# sara-n210_breakout.net
KiCad netlist of a schematic drawn in Altium Designer
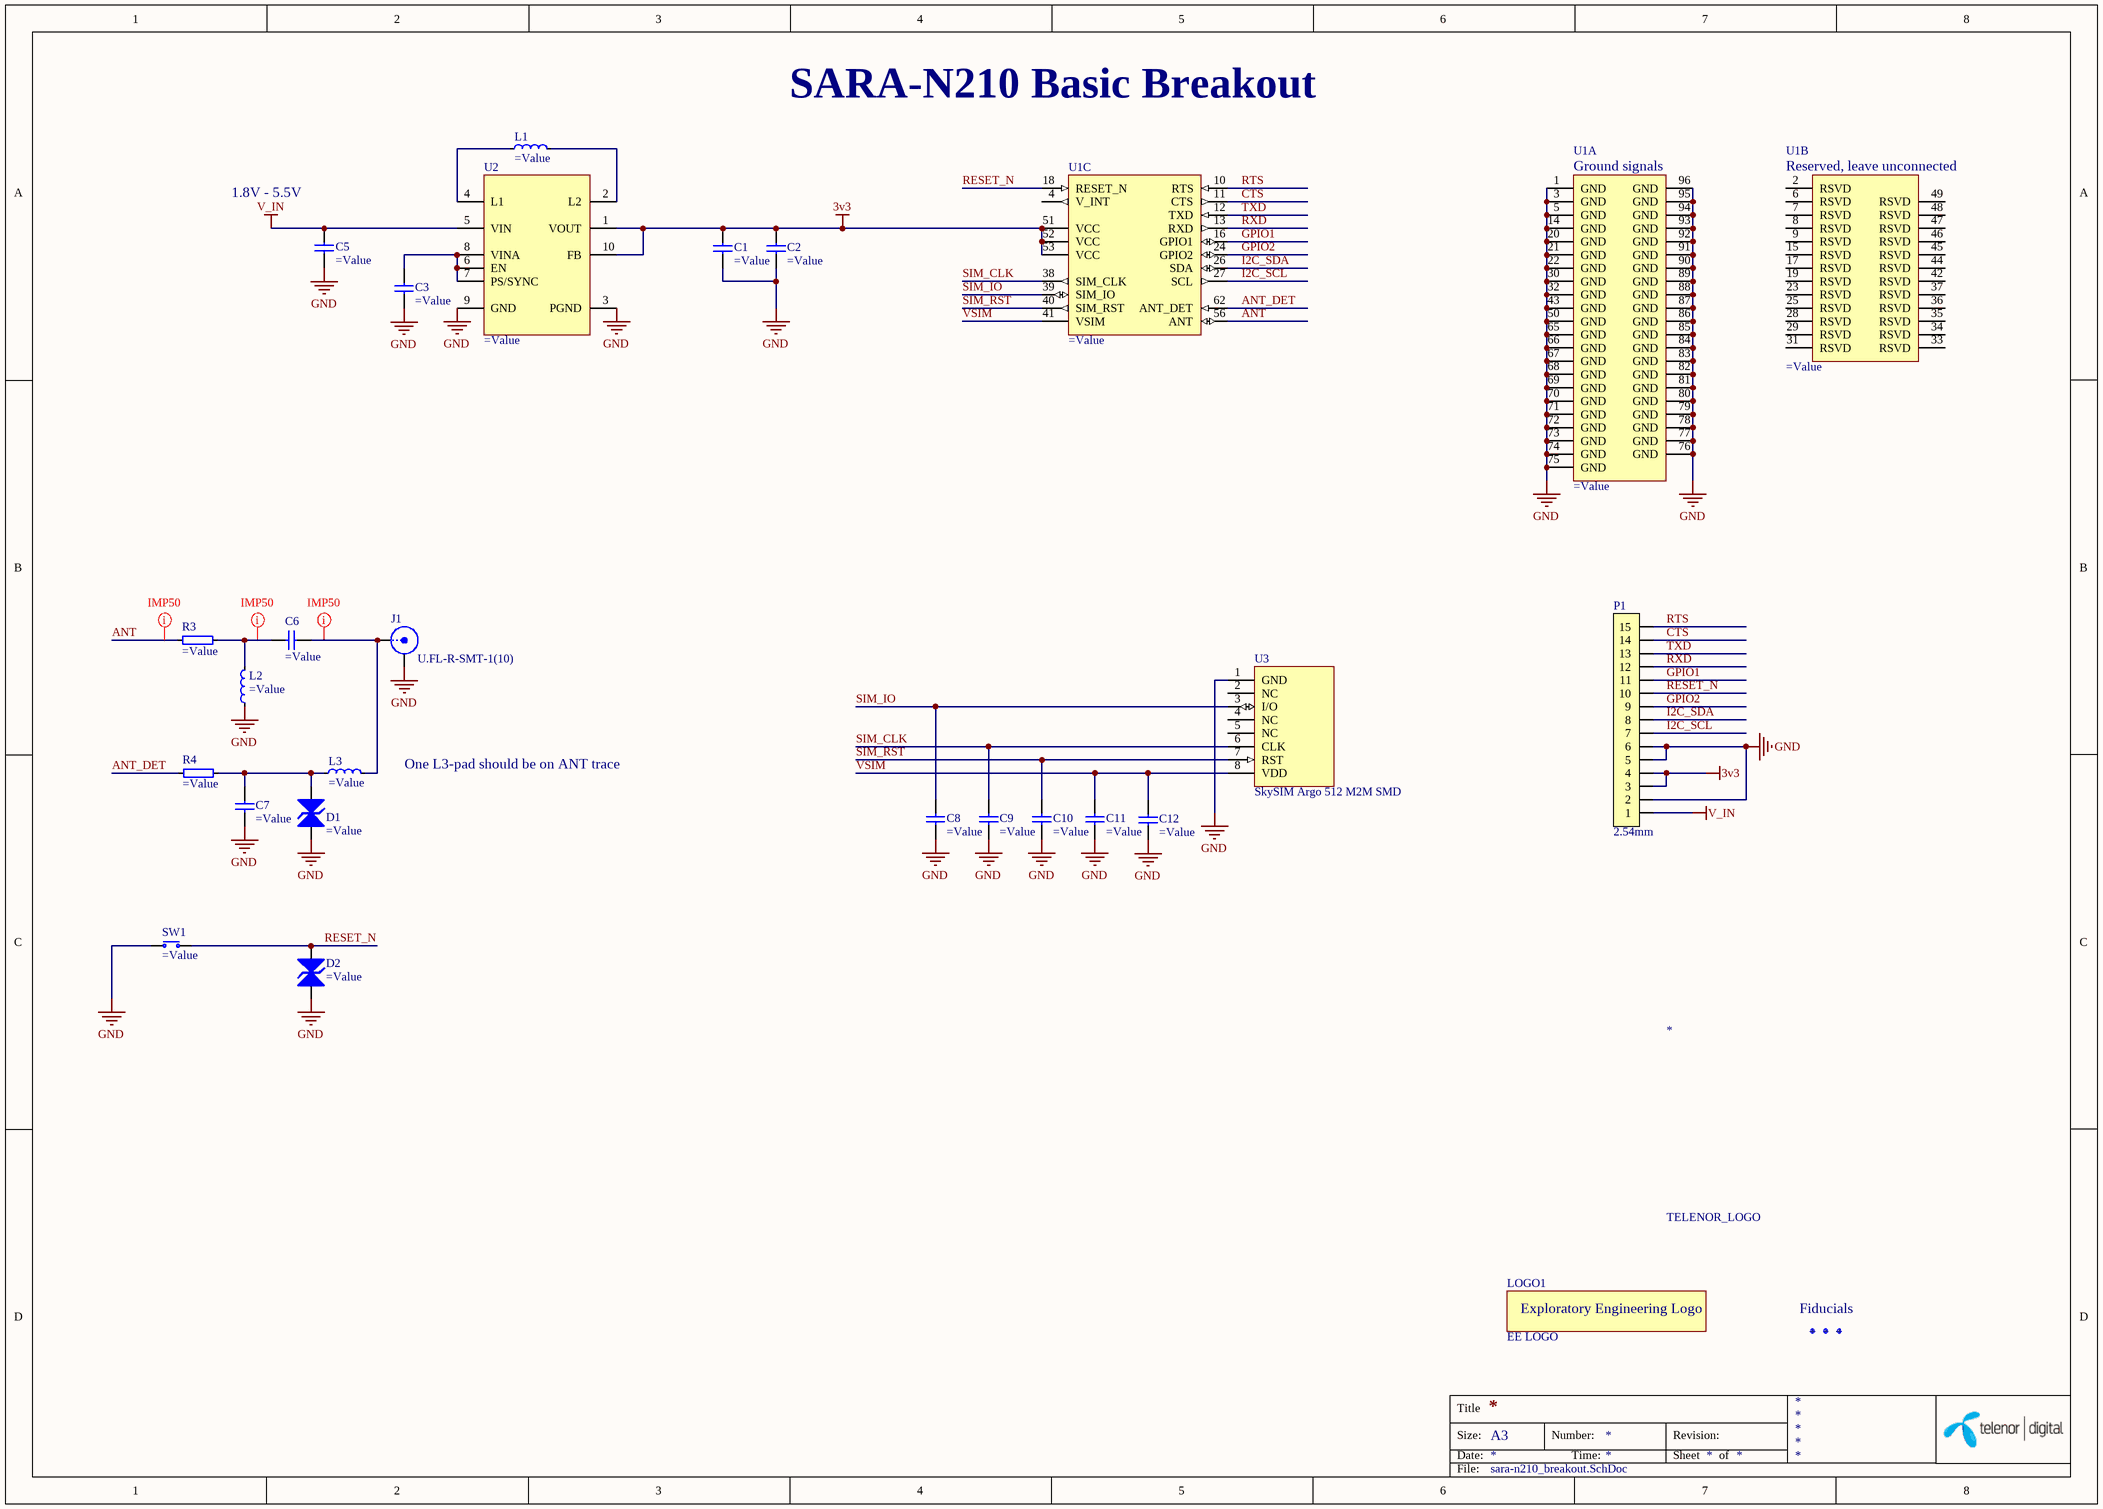
[diagram p0: sara-n210_breakout.SchDoc]

(export (version "E")
  (design (tool "Eeschema 10.0.6"))
  (components
    (comp (ref "*")
      (value "TELENOR_LOGO")
      (footprint "TELENOR_4mmx3.8mm")
      (libsource (lib "Skunkworks Library") (part "TELENOR_LOGO"))
    )
    (comp (ref "C1")
      (value "~")
      (footprint "CAPC1005X04L")
      (description "CAP CER 10UF 6.3V X5R 0402")
      (fields
        (field (name "MANUFACTURER") "Murata Electronics North America")
        (field (name "MANUFACTURER PART NUMBER") "GRM155R60J106ME15D")
      )
      (libsource (lib "Skunkworks Library") (part "GRM155R60J106ME15D"))
    )
    (comp (ref "C2")
      (value "~")
      (footprint "CAPC1005X04L")
      (description "CAP CER 10UF 6.3V X5R 0402")
      (fields
        (field (name "MANUFACTURER") "Murata Electronics North America")
        (field (name "MANUFACTURER PART NUMBER") "GRM155R60J106ME15D")
      )
      (libsource (lib "Skunkworks Library") (part "GRM155R60J106ME15D"))
    )
    (comp (ref "C3")
      (value "~")
      (footprint "CAPC1005X04L")
      (description "CAP CER 100nF 16V X7R 0402")
      (fields
        (field (name "MANUFACTURER") "Murata Electronics North America")
        (field (name "MANUFACTURER PART NUMBER") "GRM155R71C104KA88D")
      )
      (libsource (lib "Skunkworks Library") (part "GRM155R71C104KA88D"))
    )
    (comp (ref "C5")
      (value "~")
      (footprint "CAPC1005X04L")
      (description "CAP CER 10UF 6.3V X5R 0402")
      (fields
        (field (name "MANUFACTURER") "Murata Electronics North America")
        (field (name "MANUFACTURER PART NUMBER") "GRM155R60J106ME15D")
      )
      (libsource (lib "Skunkworks Library") (part "GRM155R60J106ME15D"))
    )
    (comp (ref "C6")
      (value "~")
      (footprint "CAPC1005X04L")
      (description "CAP CER 33PF 50V NP0 0402")
      (fields
        (field (name "MANUFACTURER") "Murata Electronics North America")
        (field (name "MANUFACTURER PART NUMBER") "GRM1555C1H330JZ01D")
      )
      (libsource (lib "Skunkworks Library") (part "GRM1555C1H330JZ01D"))
    )
    (comp (ref "C7")
      (value "~")
      (footprint "CAPC1005X04L")
      (description "CAP CER 27PF 50V C0G/NP0 0402")
      (fields
        (field (name "MANUFACTURER") "Murata Electronics North America")
        (field (name "MANUFACTURER PART NUMBER") "GRM1555C1H270JA01D")
      )
      (libsource (lib "Skunkworks Library") (part "GRM1555C1H270JA01D"))
    )
    (comp (ref "C8")
      (value "~")
      (footprint "CAPC1005X04L")
      (description "CAP CER 47PF 50V C0G/NP0 0402")
      (fields
        (field (name "MANUFACTURER") "Murata Electronics North America")
        (field (name "MANUFACTURER PART NUMBER") "GRM1555C1H470JA01D")
      )
      (libsource (lib "Skunkworks Library") (part "GRM1555C1H470JA01D"))
    )
    (comp (ref "C9")
      (value "~")
      (footprint "CAPC1005X04L")
      (description "CAP CER 47PF 50V C0G/NP0 0402")
      (fields
        (field (name "MANUFACTURER") "Murata Electronics North America")
        (field (name "MANUFACTURER PART NUMBER") "GRM1555C1H470JA01D")
      )
      (libsource (lib "Skunkworks Library") (part "GRM1555C1H470JA01D"))
    )
    (comp (ref "C10")
      (value "~")
      (footprint "CAPC1005X04L")
      (description "CAP CER 47PF 50V C0G/NP0 0402")
      (fields
        (field (name "MANUFACTURER") "Murata Electronics North America")
        (field (name "MANUFACTURER PART NUMBER") "GRM1555C1H470JA01D")
      )
      (libsource (lib "Skunkworks Library") (part "GRM1555C1H470JA01D"))
    )
    (comp (ref "C11")
      (value "~")
      (footprint "CAPC1005X04L")
      (description "CAP CER 47PF 50V C0G/NP0 0402")
      (fields
        (field (name "MANUFACTURER") "Murata Electronics North America")
        (field (name "MANUFACTURER PART NUMBER") "GRM1555C1H470JA01D")
      )
      (libsource (lib "Skunkworks Library") (part "GRM1555C1H470JA01D"))
    )
    (comp (ref "C12")
      (value "~")
      (footprint "CAPC1005X04L")
      (description "CAP CER 100nF 16V X7R 0402")
      (fields
        (field (name "MANUFACTURER") "Murata Electronics North America")
        (field (name "MANUFACTURER PART NUMBER") "GRM155R71C104KA88D")
      )
      (libsource (lib "Skunkworks Library") (part "GRM155R71C104KA88D"))
    )
    (comp (ref "D1")
      (value "~")
      (footprint "RESC1005X04L")
      (description "TVS DIODE 14VWM 40VC 0402")
      (fields
        (field (name "MANUFACTURER") "Littelfuse Inc.")
        (field (name "MANUFACTURER PART NUMBER") "PESD0402-140")
      )
      (libsource (lib "Skunkworks Library") (part "PESD0402-140"))
    )
    (comp (ref "D2")
      (value "~")
      (footprint "RESC1005X04L")
      (description "VARISTOR 28V 2A 0402")
      (fields
        (field (name "MANUFACTURER") "EPCOS (TDK)")
        (field (name "MANUFACTURER PART NUMBER") "B72590T8140S160")
      )
      (libsource (lib "Skunkworks Library") (part "B72590T8140S160"))
    )
    (comp (ref "Fid1")
      (value "Fiducial mark")
      (footprint "Fiducial")
      (description "Fiducial Mark")
      (fields (field (name "PART NUMBER") "Fid-Mark") (field (name "PUBLISHER") "Nordic Semiconductor"))
      (libsource (lib "Skunkworks Library") (part "Fiducial"))
    )
    (comp (ref "Fid2")
      (value "Fiducial mark")
      (footprint "Fiducial")
      (description "Fiducial Mark")
      (fields (field (name "PART NUMBER") "Fid-Mark") (field (name "PUBLISHER") "Nordic Semiconductor"))
      (libsource (lib "Skunkworks Library") (part "Fiducial"))
    )
    (comp (ref "Fid3")
      (value "Fiducial mark")
      (footprint "Fiducial")
      (description "Fiducial Mark")
      (fields (field (name "PART NUMBER") "Fid-Mark") (field (name "PUBLISHER") "Nordic Semiconductor"))
      (libsource (lib "Skunkworks Library") (part "Fiducial"))
    )
    (comp (ref "J1")
      (value "U.FL-R-SMT-1(10)")
      (footprint "COAXIAL-UFL")
      (description "CONN UMC JACK STR 50 OHM SMD")
      (fields (field (name "MANUFACTURER") "Hirose Electric Co Ltd"))
      (libsource (lib "Skunkworks Library") (part "U.FL-R-SMT-1(10)"))
    )
    (comp (ref "L1")
      (value "~")
      (footprint "INDP3030X11L")
      (description "FIXED IND 1.5UH 2.04A 88.8 MOHM")
      (fields
        (field (name "MANUFACTURER") "Murata Electronics North America")
        (field (name "MANUFACTURER PART NUMBER") "LQH3NPZ1R5MGRL")
      )
      (libsource (lib "Skunkworks Library") (part "LQH3NPZ1R5MGRL"))
    )
    (comp (ref "L2")
      (value "~")
      (footprint "INDC1005X04L")
      (description "FIXED IND 39NH 250MA 1.06 OHM")
      (fields
        (field (name "MANUFACTURER") "Murata Electronics North America")
        (field (name "MANUFACTURER PART NUMBER") "LQG15HN39NJ02D")
      )
      (libsource (lib "Skunkworks Library") (part "LQG15HN39NJ02D"))
    )
    (comp (ref "L3")
      (value "~")
      (footprint "INDC1005X04L")
      (description "FIXED IND 82NH 150MA 1.2 OHM SMD")
      (fields
        (field (name "MANUFACTURER") "Murata Electronics North America")
        (field (name "MANUFACTURER PART NUMBER") "LQG15HS82NJ02D")
      )
      (libsource (lib "Skunkworks Library") (part "LQG15HS82NJ02D"))
    )
    (comp (ref "LOGO1")
      (value "EE LOGO")
      (footprint "EE_LOGO")
      (description "Exploratory Engineering Logo Silkscreen")
      (libsource (lib "Skunkworks Library") (part "EE-LOGO"))
    )
    (comp (ref "P1")
      (value "2.54mm")
      (footprint "HDR_1x15_2.54mm_THRU")
      (description "Header, 1x15, Pitch 2.54mm, Male")
      (libsource (lib "Skunkworks Library") (part "HDR_1x15_2.54MM_MALE"))
    )
    (comp (ref "R3")
      (value "~")
      (footprint "RESC1005X04L")
      (description "RES SMD 0.0OHM JUMPER 1/16W 0402")
      (fields
        (field (name "MANUFACTURER") "Yageo")
        (field (name "MANUFACTURER PART NUMBER") "RC0402JR-070RL")
      )
      (libsource (lib "Skunkworks Library") (part "RC0402JR-070RL"))
    )
    (comp (ref "R4")
      (value "~")
      (footprint "RESC1005X04L")
      (description "RES SMD 10K OHM 1% 1/10W 0402")
      (fields
        (field (name "MANUFACTURER") "Vishay Beyschlag")
        (field (name "MANUFACTURER PART NUMBER") "MCS04020C1002FE000")
      )
      (libsource (lib "Skunkworks Library") (part "MCS04020C1002FE000"))
    )
    (comp (ref "SW1")
      (value "~")
      (footprint "RS-014R05B1-SMA10")
      (description "SWITCH TACTILE SPST-NO 0.05A 12V")
      (fields
        (field (name "MANUFACTURER") "C&K")
        (field (name "MANUFACTURER PART NUMBER") "RS-014R05B1-SMA10 RT")
      )
      (libsource (lib "Skunkworks Library") (part "RS-014R05B1-SMA10 RT"))
    )
    (comp (ref "U1")
      (value "~")
      (footprint "UB-SARA-N2")
      (description "uBlox Sara N210")
      (fields (field (name "MANUFACTURER PART NUMBER") "SARA-N210-02B"))
      (libsource (lib "Skunkworks Library") (part "SARA-N2"))
    )
    (comp (ref "U2")
      (value "~")
      (footprint "SON50P250X80_HS-11N")
      (description "IC REG BUCK BST 3.3V 0.9A 10SON")
      (fields
        (field (name "MANUFACTURER") "Texas Instruments")
        (field (name "MANUFACTURER PART NUMBER") "TPS63031DSKR")
      )
      (libsource (lib "Skunkworks Library") (part "TPS63031DSKR"))
    )
    (comp (ref "U3")
      (value "SkySIM Argo 512 M2M SMD")
      (footprint "QFN127P500X600X90_HS-9N")
      (description "SkySIM® Argo 512 M2M SMD - LTE")
      (libsource (lib "Skunkworks Library") (part "SKYSIM-ARGO-LTE-MFF2"))
    )
  )
  (nets
    (net (code "1") (name "/ANT") (class "Default")
      (node (ref "R3") (pin "1") (pinfunction "1_1") (pintype "passive"))
      (node (ref "U1") (pin "56") (pinfunction "ANT_56") (pintype "bidirectional"))
    )
    (net (code "2") (name "/ANT_DET") (class "Default")
      (node (ref "R4") (pin "1") (pinfunction "1_1") (pintype "passive"))
      (node (ref "U1") (pin "62") (pinfunction "ANT_DET_62") (pintype "input"))
    )
    (net (code "3") (name "/CTS") (class "Default")
      (node (ref "P1") (pin "14") (pinfunction "14_14") (pintype "passive"))
      (node (ref "U1") (pin "11") (pinfunction "CTS_11") (pintype "output"))
    )
    (net (code "4") (name "/GPIO1") (class "Default")
      (node (ref "P1") (pin "11") (pinfunction "11_11") (pintype "passive"))
      (node (ref "U1") (pin "16") (pinfunction "GPIO1_16") (pintype "bidirectional"))
    )
    (net (code "5") (name "/GPIO2") (class "Default")
      (node (ref "P1") (pin "9") (pinfunction "9_9") (pintype "passive"))
      (node (ref "U1") (pin "24") (pinfunction "GPIO2_24") (pintype "bidirectional"))
    )
    (net (code "6") (name "/I2C_SCL") (class "Default")
      (node (ref "P1") (pin "7") (pinfunction "7_7") (pintype "passive"))
      (node (ref "U1") (pin "27") (pinfunction "SCL_27") (pintype "output"))
    )
    (net (code "7") (name "/I2C_SDA") (class "Default")
      (node (ref "P1") (pin "8") (pinfunction "8_8") (pintype "passive"))
      (node (ref "U1") (pin "26") (pinfunction "SDA_26") (pintype "bidirectional"))
    )
    (net (code "8") (name "/RESET_N") (class "Default")
      (node (ref "D2") (pin "1") (pinfunction "A_1") (pintype "passive"))
      (node (ref "P1") (pin "10") (pinfunction "10_10") (pintype "passive"))
      (node (ref "SW1") (pin "1") (pinfunction "N.O_1") (pintype "passive"))
      (node (ref "U1") (pin "18") (pinfunction "RESET_N_18") (pintype "input"))
    )
    (net (code "9") (name "/RTS") (class "Default")
      (node (ref "P1") (pin "15") (pinfunction "15_15") (pintype "passive"))
      (node (ref "U1") (pin "10") (pinfunction "RTS_10") (pintype "input"))
    )
    (net (code "10") (name "/RXD") (class "Default")
      (node (ref "P1") (pin "12") (pinfunction "12_12") (pintype "passive"))
      (node (ref "U1") (pin "13") (pinfunction "RXD_13") (pintype "output"))
    )
    (net (code "11") (name "/SIM_CLK") (class "Default")
      (node (ref "C9") (pin "2") (pinfunction "2_2") (pintype "passive"))
      (node (ref "U1") (pin "38") (pinfunction "SIM_CLK_38") (pintype "output"))
      (node (ref "U3") (pin "6") (pinfunction "CLK_6") (pintype "passive"))
    )
    (net (code "12") (name "/SIM_IO") (class "Default")
      (node (ref "C8") (pin "2") (pinfunction "2_2") (pintype "passive"))
      (node (ref "U1") (pin "39") (pinfunction "SIM_IO_39") (pintype "bidirectional"))
      (node (ref "U3") (pin "3") (pinfunction "I/O_3") (pintype "bidirectional"))
    )
    (net (code "13") (name "/SIM_RST") (class "Default")
      (node (ref "C10") (pin "2") (pinfunction "2_2") (pintype "passive"))
      (node (ref "U1") (pin "40") (pinfunction "SIM_RST_40") (pintype "output"))
      (node (ref "U3") (pin "7") (pinfunction "RST_7") (pintype "input"))
    )
    (net (code "14") (name "/TXD") (class "Default")
      (node (ref "P1") (pin "13") (pinfunction "13_13") (pintype "passive"))
      (node (ref "U1") (pin "12") (pinfunction "TXD_12") (pintype "input"))
    )
    (net (code "15") (name "/VSIM") (class "Default")
      (node (ref "C11") (pin "2") (pinfunction "2_2") (pintype "passive"))
      (node (ref "C12") (pin "2") (pinfunction "2_2") (pintype "passive"))
      (node (ref "U1") (pin "41") (pinfunction "VSIM_41") (pintype "passive"))
      (node (ref "U3") (pin "8") (pinfunction "VDD_8") (pintype "passive"))
    )
    (net (code "16") (name "3v3") (class "Default")
      (node (ref "C1") (pin "2") (pinfunction "2_2") (pintype "passive"))
      (node (ref "C2") (pin "2") (pinfunction "2_2") (pintype "passive"))
      (node (ref "P1") (pin "3") (pinfunction "3_3") (pintype "passive"))
      (node (ref "P1") (pin "4") (pinfunction "4_4") (pintype "passive"))
      (node (ref "U1") (pin "51") (pinfunction "VCC_51") (pintype "passive"))
      (node (ref "U1") (pin "52") (pinfunction "VCC_52") (pintype "passive"))
      (node (ref "U1") (pin "53") (pinfunction "VCC_53") (pintype "passive"))
      (node (ref "U2") (pin "1") (pinfunction "VOUT_1") (pintype "passive"))
      (node (ref "U2") (pin "10") (pinfunction "FB_10") (pintype "passive"))
    )
    (net (code "17") (name "GND") (class "Default")
      (node (ref "C1") (pin "1") (pinfunction "1_1") (pintype "passive"))
      (node (ref "C10") (pin "1") (pinfunction "1_1") (pintype "passive"))
      (node (ref "C11") (pin "1") (pinfunction "1_1") (pintype "passive"))
      (node (ref "C12") (pin "1") (pinfunction "1_1") (pintype "passive"))
      (node (ref "C2") (pin "1") (pinfunction "1_1") (pintype "passive"))
      (node (ref "C3") (pin "1") (pinfunction "1_1") (pintype "passive"))
      (node (ref "C5") (pin "1") (pinfunction "1_1") (pintype "passive"))
      (node (ref "C7") (pin "2") (pinfunction "2_2") (pintype "passive"))
      (node (ref "C8") (pin "1") (pinfunction "1_1") (pintype "passive"))
      (node (ref "C9") (pin "1") (pinfunction "1_1") (pintype "passive"))
      (node (ref "D1") (pin "2") (pinfunction "K_2") (pintype "passive"))
      (node (ref "D2") (pin "2") (pinfunction "K_2") (pintype "passive"))
      (node (ref "J1") (pin "2") (pinfunction "GND_2") (pintype "passive"))
      (node (ref "L2") (pin "1") (pinfunction "1_1") (pintype "passive"))
      (node (ref "P1") (pin "2") (pinfunction "2_2") (pintype "passive"))
      (node (ref "P1") (pin "5") (pinfunction "5_5") (pintype "passive"))
      (node (ref "P1") (pin "6") (pinfunction "6_6") (pintype "passive"))
      (node (ref "SW1") (pin "2") (pinfunction "COM_2") (pintype "passive"))
      (node (ref "U1") (pin "1") (pinfunction "GND_1") (pintype "passive"))
      (node (ref "U1") (pin "14") (pinfunction "GND_14") (pintype "passive"))
      (node (ref "U1") (pin "20") (pinfunction "GND_20") (pintype "passive"))
      (node (ref "U1") (pin "21") (pinfunction "GND_21") (pintype "passive"))
      (node (ref "U1") (pin "22") (pinfunction "GND_22") (pintype "passive"))
      (node (ref "U1") (pin "3") (pinfunction "GND_3") (pintype "passive"))
      (node (ref "U1") (pin "30") (pinfunction "GND_30") (pintype "passive"))
      (node (ref "U1") (pin "32") (pinfunction "GND_32") (pintype "passive"))
      (node (ref "U1") (pin "43") (pinfunction "GND_43") (pintype "passive"))
      (node (ref "U1") (pin "5") (pinfunction "GND_5") (pintype "passive"))
      (node (ref "U1") (pin "50") (pinfunction "GND_50") (pintype "passive"))
      (node (ref "U1") (pin "65") (pinfunction "GND_65") (pintype "passive"))
      (node (ref "U1") (pin "66") (pinfunction "GND_66") (pintype "passive"))
      (node (ref "U1") (pin "67") (pinfunction "GND_67") (pintype "passive"))
      (node (ref "U1") (pin "68") (pinfunction "GND_68") (pintype "passive"))
      (node (ref "U1") (pin "69") (pinfunction "GND_69") (pintype "passive"))
      (node (ref "U1") (pin "70") (pinfunction "GND_70") (pintype "passive"))
      (node (ref "U1") (pin "71") (pinfunction "GND_71") (pintype "passive"))
      (node (ref "U1") (pin "72") (pinfunction "GND_72") (pintype "passive"))
      (node (ref "U1") (pin "73") (pinfunction "GND_73") (pintype "passive"))
      (node (ref "U1") (pin "74") (pinfunction "GND_74") (pintype "passive"))
      (node (ref "U1") (pin "75") (pinfunction "GND_75") (pintype "passive"))
      (node (ref "U1") (pin "76") (pinfunction "GND_76") (pintype "passive"))
      (node (ref "U1") (pin "77") (pinfunction "GND_77") (pintype "passive"))
      (node (ref "U1") (pin "78") (pinfunction "GND_78") (pintype "passive"))
      (node (ref "U1") (pin "79") (pinfunction "GND_79") (pintype "passive"))
      (node (ref "U1") (pin "80") (pinfunction "GND_80") (pintype "passive"))
      (node (ref "U1") (pin "81") (pinfunction "GND_81") (pintype "passive"))
      (node (ref "U1") (pin "82") (pinfunction "GND_82") (pintype "passive"))
      (node (ref "U1") (pin "83") (pinfunction "GND_83") (pintype "passive"))
      (node (ref "U1") (pin "84") (pinfunction "GND_84") (pintype "passive"))
      (node (ref "U1") (pin "85") (pinfunction "GND_85") (pintype "passive"))
      (node (ref "U1") (pin "86") (pinfunction "GND_86") (pintype "passive"))
      (node (ref "U1") (pin "87") (pinfunction "GND_87") (pintype "passive"))
      (node (ref "U1") (pin "88") (pinfunction "GND_88") (pintype "passive"))
      (node (ref "U1") (pin "89") (pinfunction "GND_89") (pintype "passive"))
      (node (ref "U1") (pin "90") (pinfunction "GND_90") (pintype "passive"))
      (node (ref "U1") (pin "91") (pinfunction "GND_91") (pintype "passive"))
      (node (ref "U1") (pin "92") (pinfunction "GND_92") (pintype "passive"))
      (node (ref "U1") (pin "93") (pinfunction "GND_93") (pintype "passive"))
      (node (ref "U1") (pin "94") (pinfunction "GND_94") (pintype "passive"))
      (node (ref "U1") (pin "95") (pinfunction "GND_95") (pintype "passive"))
      (node (ref "U1") (pin "96") (pinfunction "GND_96") (pintype "passive"))
      (node (ref "U2") (pin "3") (pinfunction "PGND_3") (pintype "passive"))
      (node (ref "U2") (pin "9") (pinfunction "GND_9") (pintype "passive"))
      (node (ref "U3") (pin "1") (pinfunction "GND_1") (pintype "passive"))
    )
    (net (code "18") (name "Net-(C6-Pad1)") (class "Default")
      (node (ref "C6") (pin "1") (pinfunction "1_1") (pintype "passive"))
      (node (ref "L2") (pin "2") (pinfunction "2_2") (pintype "passive"))
      (node (ref "R3") (pin "2") (pinfunction "2_2") (pintype "passive"))
    )
    (net (code "19") (name "Net-(D1-A)") (class "Default")
      (node (ref "C7") (pin "1") (pinfunction "1_1") (pintype "passive"))
      (node (ref "D1") (pin "1") (pinfunction "A_1") (pintype "passive"))
      (node (ref "L3") (pin "1") (pinfunction "1_1") (pintype "passive"))
      (node (ref "R4") (pin "2") (pinfunction "2_2") (pintype "passive"))
    )
    (net (code "20") (name "Net-(J1-Signal)") (class "Default")
      (node (ref "C6") (pin "2") (pinfunction "2_2") (pintype "passive"))
      (node (ref "J1") (pin "1") (pinfunction "Signal_1") (pintype "passive"))
      (node (ref "L3") (pin "2") (pinfunction "2_2") (pintype "passive"))
    )
    (net (code "21") (name "Net-(U2-EN)") (class "Default")
      (node (ref "C3") (pin "2") (pinfunction "2_2") (pintype "passive"))
      (node (ref "U2") (pin "6") (pinfunction "EN_6") (pintype "passive"))
      (node (ref "U2") (pin "7") (pinfunction "PS/SYNC_7") (pintype "passive"))
      (node (ref "U2") (pin "8") (pinfunction "VINA_8") (pintype "passive"))
    )
    (net (code "22") (name "Net-(U2-L1)") (class "Default")
      (node (ref "L1") (pin "1") (pinfunction "1_1") (pintype "passive"))
      (node (ref "U2") (pin "4") (pinfunction "L1_4") (pintype "passive"))
    )
    (net (code "23") (name "Net-(U2-L2)") (class "Default")
      (node (ref "L1") (pin "2") (pinfunction "2_2") (pintype "passive"))
      (node (ref "U2") (pin "2") (pinfunction "L2_2") (pintype "passive"))
    )
    (net (code "24") (name "V_IN") (class "Default")
      (node (ref "C5") (pin "2") (pinfunction "2_2") (pintype "passive"))
      (node (ref "P1") (pin "1") (pinfunction "1_1") (pintype "passive"))
      (node (ref "U2") (pin "5") (pinfunction "VIN_5") (pintype "passive"))
    )
    (net (code "25") (name "unconnected-(U1B-RSVD-Pad2)") (class "Default")
      (node (ref "U1") (pin "2") (pinfunction "RSVD_2") (pintype "passive"))
    )
    (net (code "26") (name "unconnected-(U1B-RSVD-Pad6)") (class "Default")
      (node (ref "U1") (pin "6") (pinfunction "RSVD_6") (pintype "passive"))
    )
    (net (code "27") (name "unconnected-(U1B-RSVD-Pad7)") (class "Default")
      (node (ref "U1") (pin "7") (pinfunction "RSVD_7") (pintype "passive"))
    )
    (net (code "28") (name "unconnected-(U1B-RSVD-Pad8)") (class "Default")
      (node (ref "U1") (pin "8") (pinfunction "RSVD_8") (pintype "passive"))
    )
    (net (code "29") (name "unconnected-(U1B-RSVD-Pad9)") (class "Default")
      (node (ref "U1") (pin "9") (pinfunction "RSVD_9") (pintype "passive"))
    )
    (net (code "30") (name "unconnected-(U1B-RSVD-Pad15)") (class "Default")
      (node (ref "U1") (pin "15") (pinfunction "RSVD_15") (pintype "passive"))
    )
    (net (code "31") (name "unconnected-(U1B-RSVD-Pad17)") (class "Default")
      (node (ref "U1") (pin "17") (pinfunction "RSVD_17") (pintype "passive"))
    )
    (net (code "32") (name "unconnected-(U1B-RSVD-Pad19)") (class "Default")
      (node (ref "U1") (pin "19") (pinfunction "RSVD_19") (pintype "passive"))
    )
    (net (code "33") (name "unconnected-(U1B-RSVD-Pad23)") (class "Default")
      (node (ref "U1") (pin "23") (pinfunction "RSVD_23") (pintype "passive"))
    )
    (net (code "34") (name "unconnected-(U1B-RSVD-Pad25)") (class "Default")
      (node (ref "U1") (pin "25") (pinfunction "RSVD_25") (pintype "passive"))
    )
    (net (code "35") (name "unconnected-(U1B-RSVD-Pad28)") (class "Default")
      (node (ref "U1") (pin "28") (pinfunction "RSVD_28") (pintype "passive"))
    )
    (net (code "36") (name "unconnected-(U1B-RSVD-Pad29)") (class "Default")
      (node (ref "U1") (pin "29") (pinfunction "RSVD_29") (pintype "passive"))
    )
    (net (code "37") (name "unconnected-(U1B-RSVD-Pad31)") (class "Default")
      (node (ref "U1") (pin "31") (pinfunction "RSVD_31") (pintype "passive"))
    )
    (net (code "38") (name "unconnected-(U1B-RSVD-Pad33)") (class "Default")
      (node (ref "U1") (pin "33") (pinfunction "RSVD_33") (pintype "passive"))
    )
    (net (code "39") (name "unconnected-(U1B-RSVD-Pad34)") (class "Default")
      (node (ref "U1") (pin "34") (pinfunction "RSVD_34") (pintype "passive"))
    )
    (net (code "40") (name "unconnected-(U1B-RSVD-Pad35)") (class "Default")
      (node (ref "U1") (pin "35") (pinfunction "RSVD_35") (pintype "passive"))
    )
    (net (code "41") (name "unconnected-(U1B-RSVD-Pad36)") (class "Default")
      (node (ref "U1") (pin "36") (pinfunction "RSVD_36") (pintype "passive"))
    )
    (net (code "42") (name "unconnected-(U1B-RSVD-Pad37)") (class "Default")
      (node (ref "U1") (pin "37") (pinfunction "RSVD_37") (pintype "passive"))
    )
    (net (code "43") (name "unconnected-(U1B-RSVD-Pad42)") (class "Default")
      (node (ref "U1") (pin "42") (pinfunction "RSVD_42") (pintype "passive"))
    )
    (net (code "44") (name "unconnected-(U1B-RSVD-Pad44)") (class "Default")
      (node (ref "U1") (pin "44") (pinfunction "RSVD_44") (pintype "passive"))
    )
    (net (code "45") (name "unconnected-(U1B-RSVD-Pad45)") (class "Default")
      (node (ref "U1") (pin "45") (pinfunction "RSVD_45") (pintype "passive"))
    )
    (net (code "46") (name "unconnected-(U1B-RSVD-Pad46)") (class "Default")
      (node (ref "U1") (pin "46") (pinfunction "RSVD_46") (pintype "passive"))
    )
    (net (code "47") (name "unconnected-(U1B-RSVD-Pad47)") (class "Default")
      (node (ref "U1") (pin "47") (pinfunction "RSVD_47") (pintype "passive"))
    )
    (net (code "48") (name "unconnected-(U1B-RSVD-Pad48)") (class "Default")
      (node (ref "U1") (pin "48") (pinfunction "RSVD_48") (pintype "passive"))
    )
    (net (code "49") (name "unconnected-(U1B-RSVD-Pad49)") (class "Default")
      (node (ref "U1") (pin "49") (pinfunction "RSVD_49") (pintype "passive"))
    )
    (net (code "50") (name "unconnected-(U1C-V_INT-Pad4)") (class "Default")
      (node (ref "U1") (pin "4") (pinfunction "V_INT_4") (pintype "output"))
    )
    (net (code "51") (name "unconnected-(U3-NC-Pad2)") (class "Default")
      (node (ref "U3") (pin "2") (pinfunction "NC_2") (pintype "passive"))
    )
    (net (code "52") (name "unconnected-(U3-NC-Pad4)") (class "Default")
      (node (ref "U3") (pin "4") (pinfunction "NC_4") (pintype "passive"))
    )
    (net (code "53") (name "unconnected-(U3-NC-Pad5)") (class "Default")
      (node (ref "U3") (pin "5") (pinfunction "NC_5") (pintype "passive"))
    )
  )
)
